# vixen-64k.net
KiCad netlist of a schematic drawn in EAGLE
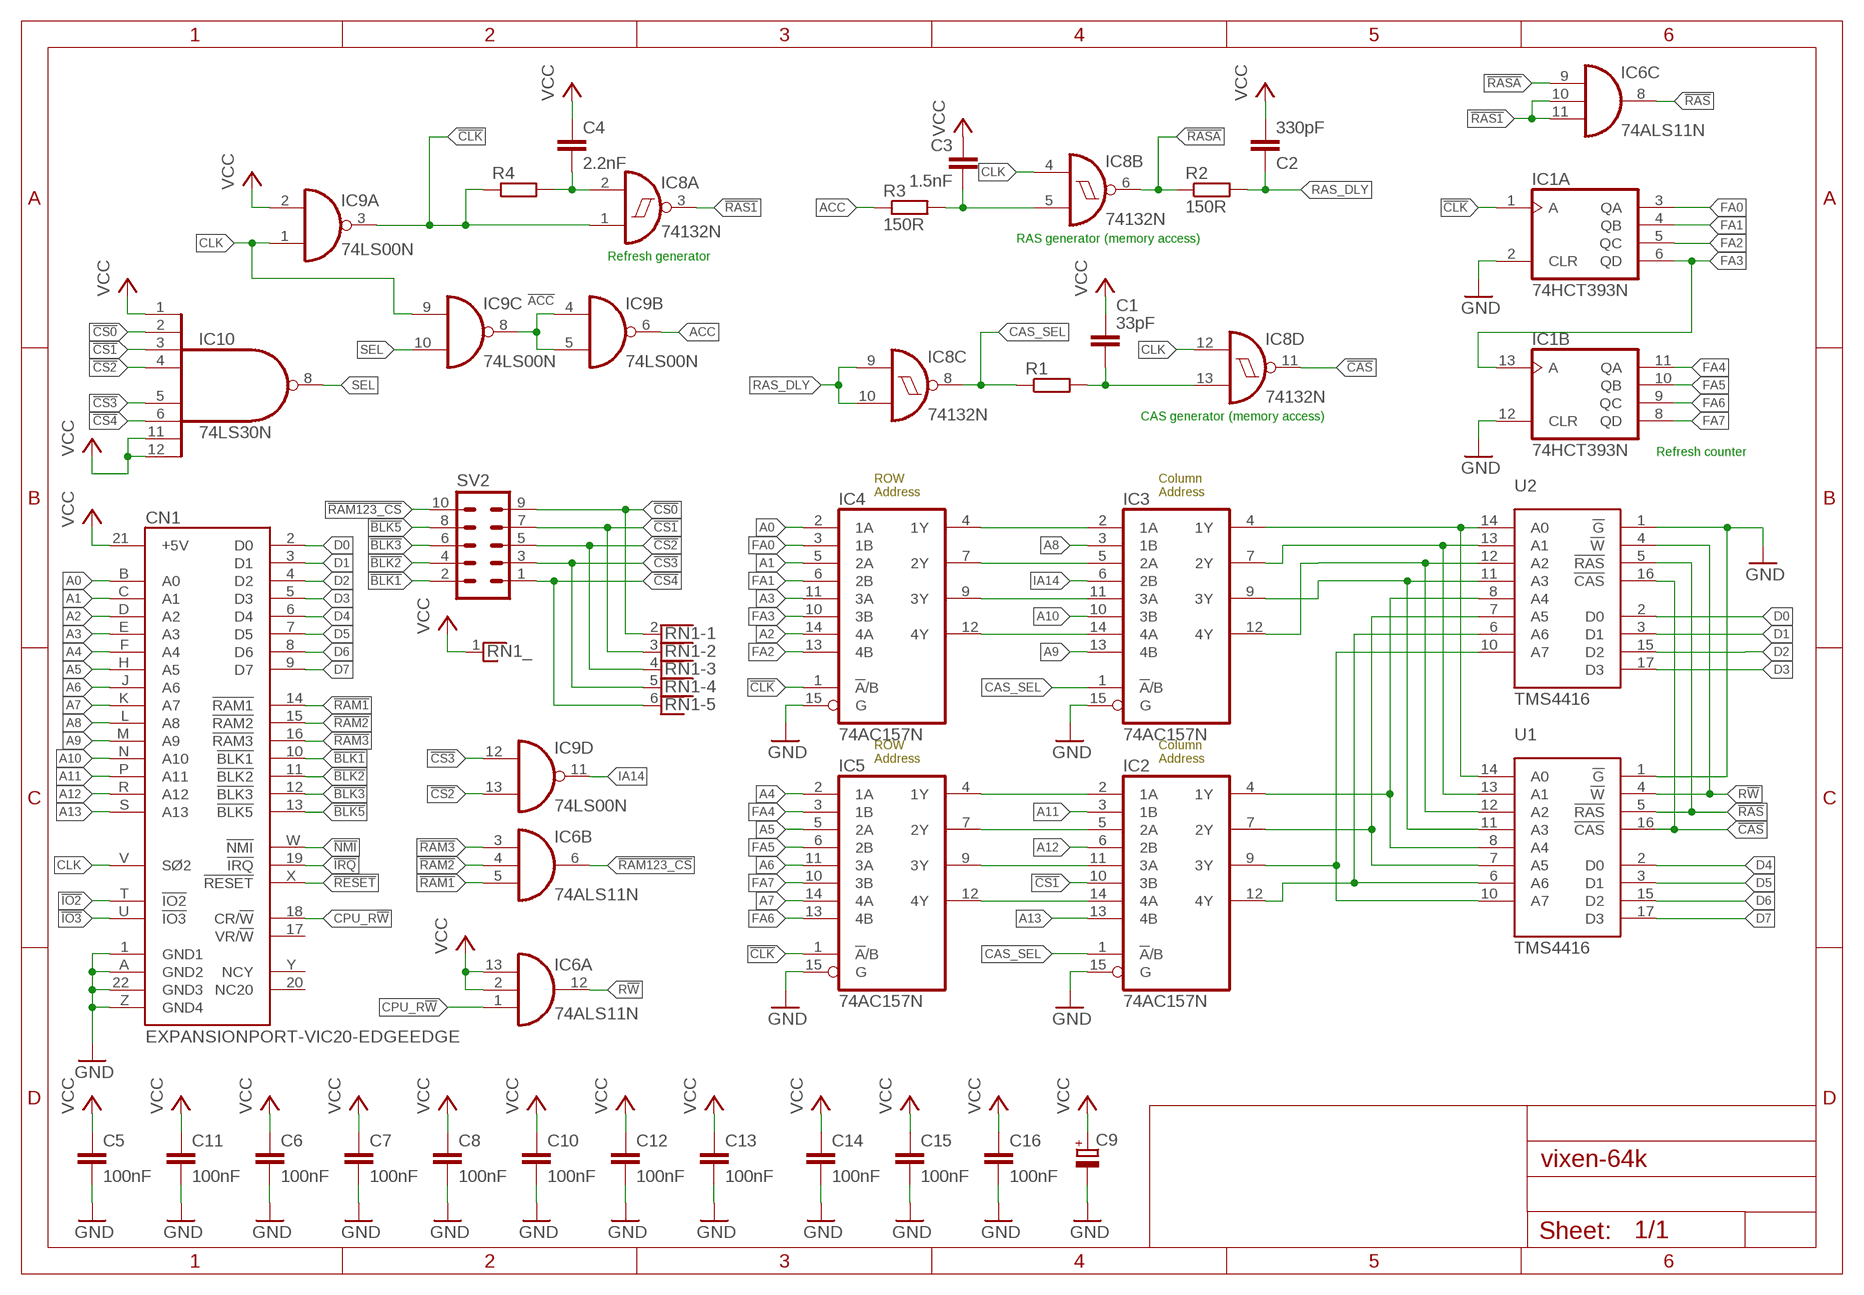
[diagram p0: schematic, sheet 1]

(export (version "E")
  (design (tool "Eeschema 10.0.6"))
  (components
    (comp (ref "C1")
      (value "33pF")
      (footprint "eagle-import:C025-025X050")
      (libsource (lib "eagle-import") (part "C-EU025-025X050"))
    )
    (comp (ref "C2")
      (value "330pF")
      (footprint "eagle-import:C025-025X050")
      (libsource (lib "eagle-import") (part "C-EU025-025X050"))
    )
    (comp (ref "C3")
      (value "1.5nF")
      (footprint "eagle-import:C025-025X050")
      (libsource (lib "eagle-import") (part "C-EU025-025X050"))
    )
    (comp (ref "C4")
      (value "2.2nF")
      (footprint "eagle-import:C025-025X050")
      (libsource (lib "eagle-import") (part "C-EU025-025X050"))
    )
    (comp (ref "C5")
      (value "100nF")
      (footprint "eagle-import:C025-025X050")
      (libsource (lib "eagle-import") (part "C-EU025-025X050"))
    )
    (comp (ref "C6")
      (value "100nF")
      (footprint "eagle-import:C025-025X050")
      (libsource (lib "eagle-import") (part "C-EU025-025X050"))
    )
    (comp (ref "C7")
      (value "100nF")
      (footprint "eagle-import:C025-025X050")
      (libsource (lib "eagle-import") (part "C-EU025-025X050"))
    )
    (comp (ref "C8")
      (value "100nF")
      (footprint "eagle-import:C025-025X050")
      (libsource (lib "eagle-import") (part "C-EU025-025X050"))
    )
    (comp (ref "C9")
      (value "CPOL-EUE15-5AXIAL")
      (footprint "eagle-import:E15-5")
      (libsource (lib "eagle-import") (part "CPOL-EUE15-5AXIAL"))
    )
    (comp (ref "C10")
      (value "100nF")
      (footprint "eagle-import:C025-025X050")
      (libsource (lib "eagle-import") (part "C-EU025-025X050"))
    )
    (comp (ref "C11")
      (value "100nF")
      (footprint "eagle-import:C025-025X050")
      (libsource (lib "eagle-import") (part "C-EU025-025X050"))
    )
    (comp (ref "C12")
      (value "100nF")
      (footprint "eagle-import:C025-025X050")
      (libsource (lib "eagle-import") (part "C-EU025-025X050"))
    )
    (comp (ref "C13")
      (value "100nF")
      (footprint "eagle-import:C025-025X050")
      (libsource (lib "eagle-import") (part "C-EU025-025X050"))
    )
    (comp (ref "C14")
      (value "100nF")
      (footprint "eagle-import:C025-025X050")
      (libsource (lib "eagle-import") (part "C-EU025-025X050"))
    )
    (comp (ref "C15")
      (value "100nF")
      (footprint "eagle-import:C025-025X050")
      (libsource (lib "eagle-import") (part "C-EU025-025X050"))
    )
    (comp (ref "C16")
      (value "100nF")
      (footprint "eagle-import:C025-025X050")
      (libsource (lib "eagle-import") (part "C-EU025-025X050"))
    )
    (comp (ref "CN1")
      (value "EXPANSIONPORT-VIC20-EDGEEDGE")
      (footprint "eagle-import:UPS44EDGE")
      (libsource (lib "eagle-import") (part "EXPANSIONPORT-VIC20-EDGEEDGE"))
    )
    (comp (ref "IC1")
      (value "74HCT393N")
      (footprint "eagle-import:DIL14")
      (libsource (lib "eagle-import") (part "74393NHCT"))
    )
    (comp (ref "IC2")
      (value "74AC157N")
      (footprint "eagle-import:DIL16")
      (libsource (lib "eagle-import") (part "74157NAC"))
    )
    (comp (ref "IC3")
      (value "74AC157N")
      (footprint "eagle-import:DIL16")
      (libsource (lib "eagle-import") (part "74157NAC"))
    )
    (comp (ref "IC4")
      (value "74AC157N")
      (footprint "eagle-import:DIL16")
      (libsource (lib "eagle-import") (part "74157NAC"))
    )
    (comp (ref "IC5")
      (value "74AC157N")
      (footprint "eagle-import:DIL16")
      (libsource (lib "eagle-import") (part "74157NAC"))
    )
    (comp (ref "IC6")
      (value "74ALS11N")
      (footprint "eagle-import:DIL14")
      (libsource (lib "eagle-import") (part "7411NALS"))
    )
    (comp (ref "IC8")
      (value "74132N")
      (footprint "eagle-import:DIL14")
      (libsource (lib "eagle-import") (part "74132N"))
    )
    (comp (ref "IC9")
      (value "74LS00N")
      (footprint "eagle-import:DIL14")
      (libsource (lib "eagle-import") (part "7400NLS"))
    )
    (comp (ref "IC10")
      (value "74LS30N")
      (footprint "eagle-import:DIL14")
      (libsource (lib "eagle-import") (part "7430NLS"))
    )
    (comp (ref "R1")
      (value "R-EU_0204/7")
      (footprint "eagle-import:0204_7")
      (libsource (lib "eagle-import") (part "R-EU_0204/7"))
    )
    (comp (ref "R2")
      (value "150R")
      (footprint "eagle-import:0204_7")
      (libsource (lib "eagle-import") (part "R-EU_0204/7"))
    )
    (comp (ref "R3")
      (value "150R")
      (footprint "eagle-import:0204_7")
      (libsource (lib "eagle-import") (part "R-EU_0204/7"))
    )
    (comp (ref "R4")
      (value "R-EU_0204/7")
      (footprint "eagle-import:0204_7")
      (libsource (lib "eagle-import") (part "R-EU_0204/7"))
    )
    (comp (ref "RN1")
      (value "RNX5")
      (footprint "eagle-import:RN-6")
      (libsource (lib "eagle-import") (part "RNX5"))
    )
    (comp (ref "SV2")
      (value "MA05-2")
      (footprint "eagle-import:MA05-2")
      (libsource (lib "eagle-import") (part "MA05-2"))
    )
    (comp (ref "U1")
      (value "TMS4416")
      (footprint "eagle-import:DIL18")
      (libsource (lib "eagle-import") (part "TMS4416"))
    )
    (comp (ref "U2")
      (value "TMS4416")
      (footprint "eagle-import:DIL18")
      (libsource (lib "eagle-import") (part "TMS4416"))
    )
  )
  (nets
    (net (code "1") (name "/CPU_R~{W}") (class "Default")
      (node (ref "CN1") (pin "18") (pinfunction "CR/~{W}_18") (pintype "output"))
      (node (ref "IC6") (pin "1") (pinfunction "I0_1") (pintype "input"))
    )
    (net (code "2") (name "/R~{W}") (class "Default")
      (node (ref "IC6") (pin "12") (pinfunction "O_12") (pintype "output"))
      (node (ref "U1") (pin "4") (pinfunction "~{W}_4") (pintype "bidirectional"))
      (node (ref "U2") (pin "4") (pinfunction "~{W}_4") (pintype "bidirectional"))
    )
    (net (code "3") (name "/~{ACC}") (class "Default")
      (node (ref "IC9") (pin "4") (pinfunction "I0_4") (pintype "input"))
      (node (ref "IC9") (pin "5") (pinfunction "I1_5") (pintype "input"))
      (node (ref "IC9") (pin "8") (pinfunction "O_8") (pintype "output"))
    )
    (net (code "4") (name "/~{BLK1}") (class "Default")
      (node (ref "CN1") (pin "10") (pinfunction "~{BLK1}_10") (pintype "output"))
      (node (ref "SV2") (pin "2") (pinfunction "2_2") (pintype "passive"))
    )
    (net (code "5") (name "/~{BLK2}") (class "Default")
      (node (ref "CN1") (pin "11") (pinfunction "~{BLK2}_11") (pintype "output"))
      (node (ref "SV2") (pin "4") (pinfunction "4_4") (pintype "passive"))
    )
    (net (code "6") (name "/~{BLK3}") (class "Default")
      (node (ref "CN1") (pin "12") (pinfunction "~{BLK3}_12") (pintype "output"))
      (node (ref "SV2") (pin "6") (pinfunction "6_6") (pintype "passive"))
    )
    (net (code "7") (name "/~{BLK5}") (class "Default")
      (node (ref "CN1") (pin "13") (pinfunction "~{BLK5}_13") (pintype "output"))
      (node (ref "SV2") (pin "8") (pinfunction "8_8") (pintype "passive"))
    )
    (net (code "8") (name "/~{CAS}") (class "Default")
      (node (ref "IC8") (pin "11") (pinfunction "O_11") (pintype "output"))
      (node (ref "U1") (pin "16") (pinfunction "~{CAS}_16") (pintype "bidirectional"))
      (node (ref "U2") (pin "16") (pinfunction "~{CAS}_16") (pintype "bidirectional"))
    )
    (net (code "9") (name "/~{CLK}") (class "Default")
      (node (ref "IC1") (pin "1") (pinfunction "A_1") (pintype "input"))
      (node (ref "IC4") (pin "1") (pinfunction "~{A}/B_1") (pintype "input"))
      (node (ref "IC5") (pin "1") (pinfunction "~{A}/B_1") (pintype "input"))
      (node (ref "IC8") (pin "1") (pinfunction "I0_1") (pintype "input"))
      (node (ref "IC9") (pin "3") (pinfunction "O_3") (pintype "output"))
      (node (ref "R4") (pin "1") (pinfunction "1_1") (pintype "passive"))
    )
    (net (code "10") (name "/~{CS0}") (class "Default")
      (node (ref "IC10") (pin "2") (pinfunction "I1_2") (pintype "input"))
      (node (ref "RN1") (pin "2") (pinfunction "1_2") (pintype "passive"))
      (node (ref "SV2") (pin "9") (pinfunction "9_9") (pintype "passive"))
    )
    (net (code "11") (name "/~{CS1}") (class "Default")
      (node (ref "IC10") (pin "3") (pinfunction "I2_3") (pintype "input"))
      (node (ref "IC2") (pin "10") (pinfunction "3B_10") (pintype "input"))
      (node (ref "RN1") (pin "3") (pinfunction "1_3") (pintype "passive"))
      (node (ref "SV2") (pin "7") (pinfunction "7_7") (pintype "passive"))
    )
    (net (code "12") (name "/~{CS2}") (class "Default")
      (node (ref "IC10") (pin "4") (pinfunction "I3_4") (pintype "input"))
      (node (ref "IC9") (pin "13") (pinfunction "I1_13") (pintype "input"))
      (node (ref "RN1") (pin "4") (pinfunction "1_4") (pintype "passive"))
      (node (ref "SV2") (pin "5") (pinfunction "5_5") (pintype "passive"))
    )
    (net (code "13") (name "/~{CS3}") (class "Default")
      (node (ref "IC10") (pin "5") (pinfunction "I4_5") (pintype "input"))
      (node (ref "IC9") (pin "12") (pinfunction "I0_12") (pintype "input"))
      (node (ref "RN1") (pin "5") (pinfunction "1_5") (pintype "passive"))
      (node (ref "SV2") (pin "3") (pinfunction "3_3") (pintype "passive"))
    )
    (net (code "14") (name "/~{CS4}") (class "Default")
      (node (ref "IC10") (pin "6") (pinfunction "I5_6") (pintype "input"))
      (node (ref "RN1") (pin "6") (pinfunction "1_6") (pintype "passive"))
      (node (ref "SV2") (pin "1") (pinfunction "1_1") (pintype "passive"))
    )
    (net (code "15") (name "/~{IO2}") (class "Default")
      (node (ref "CN1") (pin "T") (pinfunction "~{IO2}_T") (pintype "output"))
    )
    (net (code "16") (name "/~{IO3}") (class "Default")
      (node (ref "CN1") (pin "U") (pinfunction "~{IO3}_U") (pintype "output"))
    )
    (net (code "17") (name "/~{IRQ}") (class "Default")
      (node (ref "CN1") (pin "19") (pinfunction "~{IRQ}_19") (pintype "bidirectional"))
    )
    (net (code "18") (name "/~{NMI}") (class "Default")
      (node (ref "CN1") (pin "W") (pinfunction "~{NMI}_W") (pintype "bidirectional"))
    )
    (net (code "19") (name "/~{RAM1}") (class "Default")
      (node (ref "CN1") (pin "14") (pinfunction "~{RAM1}_14") (pintype "output"))
      (node (ref "IC6") (pin "5") (pinfunction "I2_5") (pintype "input"))
    )
    (net (code "20") (name "/~{RAM2}") (class "Default")
      (node (ref "CN1") (pin "15") (pinfunction "~{RAM2}_15") (pintype "output"))
      (node (ref "IC6") (pin "4") (pinfunction "I1_4") (pintype "input"))
    )
    (net (code "21") (name "/~{RAM3}") (class "Default")
      (node (ref "CN1") (pin "16") (pinfunction "~{RAM3}_16") (pintype "output"))
      (node (ref "IC6") (pin "3") (pinfunction "I0_3") (pintype "input"))
    )
    (net (code "22") (name "/~{RAM123_CS}") (class "Default")
      (node (ref "IC6") (pin "6") (pinfunction "O_6") (pintype "output"))
      (node (ref "SV2") (pin "10") (pinfunction "10_10") (pintype "passive"))
    )
    (net (code "23") (name "/~{RAS1}") (class "Default")
      (node (ref "IC6") (pin "10") (pinfunction "I1_10") (pintype "input"))
      (node (ref "IC6") (pin "11") (pinfunction "I2_11") (pintype "input"))
      (node (ref "IC8") (pin "3") (pinfunction "O_3") (pintype "output"))
    )
    (net (code "24") (name "/~{RASA}") (class "Default")
      (node (ref "IC6") (pin "9") (pinfunction "I0_9") (pintype "input"))
      (node (ref "IC8") (pin "6") (pinfunction "O_6") (pintype "output"))
      (node (ref "R2") (pin "1") (pinfunction "1_1") (pintype "passive"))
    )
    (net (code "25") (name "/~{RAS}") (class "Default")
      (node (ref "IC6") (pin "8") (pinfunction "O_8") (pintype "output"))
      (node (ref "U1") (pin "5") (pinfunction "~{RAS}_5") (pintype "bidirectional"))
      (node (ref "U2") (pin "5") (pinfunction "~{RAS}_5") (pintype "bidirectional"))
    )
    (net (code "26") (name "/~{RESET}") (class "Default")
      (node (ref "CN1") (pin "X") (pinfunction "~{RESET}_X") (pintype "bidirectional"))
    )
    (net (code "27") (name "A0") (class "Default")
      (node (ref "CN1") (pin "B") (pinfunction "A0_B") (pintype "output"))
      (node (ref "IC4") (pin "2") (pinfunction "1A_2") (pintype "input"))
    )
    (net (code "28") (name "A1") (class "Default")
      (node (ref "CN1") (pin "C") (pinfunction "A1_C") (pintype "output"))
      (node (ref "IC4") (pin "5") (pinfunction "2A_5") (pintype "input"))
    )
    (net (code "29") (name "A2") (class "Default")
      (node (ref "CN1") (pin "D") (pinfunction "A2_D") (pintype "output"))
      (node (ref "IC4") (pin "14") (pinfunction "4A_14") (pintype "input"))
    )
    (net (code "30") (name "A3") (class "Default")
      (node (ref "CN1") (pin "E") (pinfunction "A3_E") (pintype "output"))
      (node (ref "IC4") (pin "11") (pinfunction "3A_11") (pintype "input"))
    )
    (net (code "31") (name "A4") (class "Default")
      (node (ref "CN1") (pin "F") (pinfunction "A4_F") (pintype "output"))
      (node (ref "IC5") (pin "2") (pinfunction "1A_2") (pintype "input"))
    )
    (net (code "32") (name "A5") (class "Default")
      (node (ref "CN1") (pin "H") (pinfunction "A5_H") (pintype "output"))
      (node (ref "IC5") (pin "5") (pinfunction "2A_5") (pintype "input"))
    )
    (net (code "33") (name "A6") (class "Default")
      (node (ref "CN1") (pin "J") (pinfunction "A6_J") (pintype "output"))
      (node (ref "IC5") (pin "11") (pinfunction "3A_11") (pintype "input"))
    )
    (net (code "34") (name "A7") (class "Default")
      (node (ref "CN1") (pin "K") (pinfunction "A7_K") (pintype "output"))
      (node (ref "IC5") (pin "14") (pinfunction "4A_14") (pintype "input"))
    )
    (net (code "35") (name "A8") (class "Default")
      (node (ref "CN1") (pin "L") (pinfunction "A8_L") (pintype "output"))
      (node (ref "IC3") (pin "3") (pinfunction "1B_3") (pintype "input"))
    )
    (net (code "36") (name "A9") (class "Default")
      (node (ref "CN1") (pin "M") (pinfunction "A9_M") (pintype "output"))
      (node (ref "IC3") (pin "13") (pinfunction "4B_13") (pintype "input"))
    )
    (net (code "37") (name "A10") (class "Default")
      (node (ref "CN1") (pin "N") (pinfunction "A10_N") (pintype "output"))
      (node (ref "IC3") (pin "10") (pinfunction "3B_10") (pintype "input"))
    )
    (net (code "38") (name "A11") (class "Default")
      (node (ref "CN1") (pin "P") (pinfunction "A11_P") (pintype "output"))
      (node (ref "IC2") (pin "3") (pinfunction "1B_3") (pintype "input"))
    )
    (net (code "39") (name "A12") (class "Default")
      (node (ref "CN1") (pin "R") (pinfunction "A12_R") (pintype "output"))
      (node (ref "IC2") (pin "6") (pinfunction "2B_6") (pintype "input"))
    )
    (net (code "40") (name "A13") (class "Default")
      (node (ref "CN1") (pin "S") (pinfunction "A13_S") (pintype "output"))
      (node (ref "IC2") (pin "13") (pinfunction "4B_13") (pintype "input"))
    )
    (net (code "41") (name "ACC") (class "Default")
      (node (ref "IC9") (pin "6") (pinfunction "O_6") (pintype "output"))
      (node (ref "R3") (pin "1") (pinfunction "1_1") (pintype "passive"))
    )
    (net (code "42") (name "CAS_SEL") (class "Default")
      (node (ref "IC2") (pin "1") (pinfunction "~{A}/B_1") (pintype "input"))
      (node (ref "IC3") (pin "1") (pinfunction "~{A}/B_1") (pintype "input"))
      (node (ref "IC8") (pin "8") (pinfunction "O_8") (pintype "output"))
      (node (ref "R1") (pin "1") (pinfunction "1_1") (pintype "passive"))
    )
    (net (code "43") (name "CLK") (class "Default")
      (node (ref "CN1") (pin "V") (pinfunction "SØ2_V") (pintype "output"))
      (node (ref "IC8") (pin "12") (pinfunction "I0_12") (pintype "input"))
      (node (ref "IC8") (pin "4") (pinfunction "I0_4") (pintype "input"))
      (node (ref "IC9") (pin "1") (pinfunction "I0_1") (pintype "input"))
      (node (ref "IC9") (pin "9") (pinfunction "I0_9") (pintype "input"))
    )
    (net (code "44") (name "D0") (class "Default")
      (node (ref "CN1") (pin "2") (pinfunction "D0_2") (pintype "bidirectional"))
      (node (ref "U2") (pin "2") (pinfunction "D0_2") (pintype "bidirectional"))
    )
    (net (code "45") (name "D1") (class "Default")
      (node (ref "CN1") (pin "3") (pinfunction "D1_3") (pintype "bidirectional"))
      (node (ref "U2") (pin "3") (pinfunction "D1_3") (pintype "bidirectional"))
    )
    (net (code "46") (name "D2") (class "Default")
      (node (ref "CN1") (pin "4") (pinfunction "D2_4") (pintype "bidirectional"))
      (node (ref "U2") (pin "15") (pinfunction "D2_15") (pintype "bidirectional"))
    )
    (net (code "47") (name "D3") (class "Default")
      (node (ref "CN1") (pin "5") (pinfunction "D3_5") (pintype "bidirectional"))
      (node (ref "U2") (pin "17") (pinfunction "D3_17") (pintype "bidirectional"))
    )
    (net (code "48") (name "D4") (class "Default")
      (node (ref "CN1") (pin "6") (pinfunction "D4_6") (pintype "bidirectional"))
      (node (ref "U1") (pin "2") (pinfunction "D0_2") (pintype "bidirectional"))
    )
    (net (code "49") (name "D5") (class "Default")
      (node (ref "CN1") (pin "7") (pinfunction "D5_7") (pintype "bidirectional"))
      (node (ref "U1") (pin "3") (pinfunction "D1_3") (pintype "bidirectional"))
    )
    (net (code "50") (name "D6") (class "Default")
      (node (ref "CN1") (pin "8") (pinfunction "D6_8") (pintype "bidirectional"))
      (node (ref "U1") (pin "15") (pinfunction "D2_15") (pintype "bidirectional"))
    )
    (net (code "51") (name "D7") (class "Default")
      (node (ref "CN1") (pin "9") (pinfunction "D7_9") (pintype "bidirectional"))
      (node (ref "U1") (pin "17") (pinfunction "D3_17") (pintype "bidirectional"))
    )
    (net (code "52") (name "FA0") (class "Default")
      (node (ref "IC1") (pin "3") (pinfunction "QA_3") (pintype "output"))
      (node (ref "IC4") (pin "3") (pinfunction "1B_3") (pintype "input"))
    )
    (net (code "53") (name "FA1") (class "Default")
      (node (ref "IC1") (pin "4") (pinfunction "QB_4") (pintype "output"))
      (node (ref "IC4") (pin "6") (pinfunction "2B_6") (pintype "input"))
    )
    (net (code "54") (name "FA2") (class "Default")
      (node (ref "IC1") (pin "5") (pinfunction "QC_5") (pintype "output"))
      (node (ref "IC4") (pin "13") (pinfunction "4B_13") (pintype "input"))
    )
    (net (code "55") (name "FA3") (class "Default")
      (node (ref "IC1") (pin "13") (pinfunction "A_13") (pintype "input"))
      (node (ref "IC1") (pin "6") (pinfunction "QD_6") (pintype "output"))
      (node (ref "IC4") (pin "10") (pinfunction "3B_10") (pintype "input"))
    )
    (net (code "56") (name "FA4") (class "Default")
      (node (ref "IC1") (pin "11") (pinfunction "QA_11") (pintype "output"))
      (node (ref "IC5") (pin "3") (pinfunction "1B_3") (pintype "input"))
    )
    (net (code "57") (name "FA5") (class "Default")
      (node (ref "IC1") (pin "10") (pinfunction "QB_10") (pintype "output"))
      (node (ref "IC5") (pin "6") (pinfunction "2B_6") (pintype "input"))
    )
    (net (code "58") (name "FA6") (class "Default")
      (node (ref "IC1") (pin "9") (pinfunction "QC_9") (pintype "output"))
      (node (ref "IC5") (pin "13") (pinfunction "4B_13") (pintype "input"))
    )
    (net (code "59") (name "FA7") (class "Default")
      (node (ref "IC1") (pin "8") (pinfunction "QD_8") (pintype "output"))
      (node (ref "IC5") (pin "10") (pinfunction "3B_10") (pintype "input"))
    )
    (net (code "60") (name "GND") (class "Default")
      (node (ref "C10") (pin "2") (pinfunction "2_2") (pintype "passive"))
      (node (ref "C11") (pin "2") (pinfunction "2_2") (pintype "passive"))
      (node (ref "C12") (pin "2") (pinfunction "2_2") (pintype "passive"))
      (node (ref "C13") (pin "2") (pinfunction "2_2") (pintype "passive"))
      (node (ref "C14") (pin "2") (pinfunction "2_2") (pintype "passive"))
      (node (ref "C15") (pin "2") (pinfunction "2_2") (pintype "passive"))
      (node (ref "C16") (pin "2") (pinfunction "2_2") (pintype "passive"))
      (node (ref "C5") (pin "2") (pinfunction "2_2") (pintype "passive"))
      (node (ref "C6") (pin "2") (pinfunction "2_2") (pintype "passive"))
      (node (ref "C7") (pin "2") (pinfunction "2_2") (pintype "passive"))
      (node (ref "C8") (pin "2") (pinfunction "2_2") (pintype "passive"))
      (node (ref "C9") (pin "-") (pinfunction "-_-") (pintype "passive"))
      (node (ref "CN1") (pin "1") (pinfunction "GND1_1") (pintype "passive"))
      (node (ref "CN1") (pin "22") (pinfunction "GND3_22") (pintype "passive"))
      (node (ref "CN1") (pin "A") (pinfunction "GND2_A") (pintype "passive"))
      (node (ref "CN1") (pin "Z") (pinfunction "GND4_Z") (pintype "passive"))
      (node (ref "IC1") (pin "12") (pinfunction "CLR_12") (pintype "input"))
      (node (ref "IC1") (pin "2") (pinfunction "CLR_2") (pintype "input"))
      (node (ref "IC2") (pin "15") (pinfunction "G_15") (pintype "input"))
      (node (ref "IC3") (pin "15") (pinfunction "G_15") (pintype "input"))
      (node (ref "IC4") (pin "15") (pinfunction "G_15") (pintype "input"))
      (node (ref "IC5") (pin "15") (pinfunction "G_15") (pintype "input"))
      (node (ref "U1") (pin "1") (pinfunction "~{G}_1") (pintype "bidirectional"))
      (node (ref "U2") (pin "1") (pinfunction "~{G}_1") (pintype "bidirectional"))
    )
    (net (code "61") (name "IA14") (class "Default")
      (node (ref "IC3") (pin "6") (pinfunction "2B_6") (pintype "input"))
      (node (ref "IC9") (pin "11") (pinfunction "O_11") (pintype "output"))
    )
    (net (code "62") (name "Net-(IC2A-1A)") (class "Default")
      (node (ref "IC2") (pin "2") (pinfunction "1A_2") (pintype "input"))
      (node (ref "IC5") (pin "4") (pinfunction "1Y_4") (pintype "output"))
    )
    (net (code "63") (name "Net-(IC2A-1Y)") (class "Default")
      (node (ref "IC2") (pin "4") (pinfunction "1Y_4") (pintype "output"))
      (node (ref "U1") (pin "8") (pinfunction "A4_8") (pintype "input"))
      (node (ref "U2") (pin "8") (pinfunction "A4_8") (pintype "input"))
    )
    (net (code "64") (name "Net-(IC2A-2A)") (class "Default")
      (node (ref "IC2") (pin "5") (pinfunction "2A_5") (pintype "input"))
      (node (ref "IC5") (pin "7") (pinfunction "2Y_7") (pintype "output"))
    )
    (net (code "65") (name "Net-(IC2A-2Y)") (class "Default")
      (node (ref "IC2") (pin "7") (pinfunction "2Y_7") (pintype "output"))
      (node (ref "U1") (pin "7") (pinfunction "A5_7") (pintype "input"))
      (node (ref "U2") (pin "7") (pinfunction "A5_7") (pintype "input"))
    )
    (net (code "66") (name "Net-(IC2A-3A)") (class "Default")
      (node (ref "IC2") (pin "11") (pinfunction "3A_11") (pintype "input"))
      (node (ref "IC5") (pin "9") (pinfunction "3Y_9") (pintype "output"))
    )
    (net (code "67") (name "Net-(IC2A-3Y)") (class "Default")
      (node (ref "IC2") (pin "9") (pinfunction "3Y_9") (pintype "output"))
      (node (ref "U1") (pin "10") (pinfunction "A7_10") (pintype "input"))
      (node (ref "U2") (pin "10") (pinfunction "A7_10") (pintype "input"))
    )
    (net (code "68") (name "Net-(IC2A-4A)") (class "Default")
      (node (ref "IC2") (pin "14") (pinfunction "4A_14") (pintype "input"))
      (node (ref "IC5") (pin "12") (pinfunction "4Y_12") (pintype "output"))
    )
    (net (code "69") (name "Net-(IC2A-4Y)") (class "Default")
      (node (ref "IC2") (pin "12") (pinfunction "4Y_12") (pintype "output"))
      (node (ref "U1") (pin "6") (pinfunction "A6_6") (pintype "input"))
      (node (ref "U2") (pin "6") (pinfunction "A6_6") (pintype "input"))
    )
    (net (code "70") (name "Net-(IC3A-1A)") (class "Default")
      (node (ref "IC3") (pin "2") (pinfunction "1A_2") (pintype "input"))
      (node (ref "IC4") (pin "4") (pinfunction "1Y_4") (pintype "output"))
    )
    (net (code "71") (name "Net-(IC3A-1Y)") (class "Default")
      (node (ref "IC3") (pin "4") (pinfunction "1Y_4") (pintype "output"))
      (node (ref "U1") (pin "14") (pinfunction "A0_14") (pintype "input"))
      (node (ref "U2") (pin "14") (pinfunction "A0_14") (pintype "input"))
    )
    (net (code "72") (name "Net-(IC3A-2A)") (class "Default")
      (node (ref "IC3") (pin "5") (pinfunction "2A_5") (pintype "input"))
      (node (ref "IC4") (pin "7") (pinfunction "2Y_7") (pintype "output"))
    )
    (net (code "73") (name "Net-(IC3A-2Y)") (class "Default")
      (node (ref "IC3") (pin "7") (pinfunction "2Y_7") (pintype "output"))
      (node (ref "U1") (pin "13") (pinfunction "A1_13") (pintype "input"))
      (node (ref "U2") (pin "13") (pinfunction "A1_13") (pintype "input"))
    )
    (net (code "74") (name "Net-(IC3A-3A)") (class "Default")
      (node (ref "IC3") (pin "11") (pinfunction "3A_11") (pintype "input"))
      (node (ref "IC4") (pin "9") (pinfunction "3Y_9") (pintype "output"))
    )
    (net (code "75") (name "Net-(IC3A-3Y)") (class "Default")
      (node (ref "IC3") (pin "9") (pinfunction "3Y_9") (pintype "output"))
      (node (ref "U1") (pin "11") (pinfunction "A3_11") (pintype "input"))
      (node (ref "U2") (pin "11") (pinfunction "A3_11") (pintype "input"))
    )
    (net (code "76") (name "Net-(IC3A-4A)") (class "Default")
      (node (ref "IC3") (pin "14") (pinfunction "4A_14") (pintype "input"))
      (node (ref "IC4") (pin "12") (pinfunction "4Y_12") (pintype "output"))
    )
    (net (code "77") (name "Net-(IC3A-4Y)") (class "Default")
      (node (ref "IC3") (pin "12") (pinfunction "4Y_12") (pintype "output"))
      (node (ref "U1") (pin "12") (pinfunction "A2_12") (pintype "input"))
      (node (ref "U2") (pin "12") (pinfunction "A2_12") (pintype "input"))
    )
    (net (code "78") (name "Net-(IC8A-I1)") (class "Default")
      (node (ref "C4") (pin "2") (pinfunction "2_2") (pintype "passive"))
      (node (ref "IC8") (pin "2") (pinfunction "I1_2") (pintype "input"))
      (node (ref "R4") (pin "2") (pinfunction "2_2") (pintype "passive"))
    )
    (net (code "79") (name "Net-(IC8B-I1)") (class "Default")
      (node (ref "C3") (pin "2") (pinfunction "2_2") (pintype "passive"))
      (node (ref "IC8") (pin "5") (pinfunction "I1_5") (pintype "input"))
      (node (ref "R3") (pin "2") (pinfunction "2_2") (pintype "passive"))
    )
    (net (code "80") (name "Net-(IC8D-I1)") (class "Default")
      (node (ref "C1") (pin "2") (pinfunction "2_2") (pintype "passive"))
      (node (ref "IC8") (pin "13") (pinfunction "I1_13") (pintype "input"))
      (node (ref "R1") (pin "2") (pinfunction "2_2") (pintype "passive"))
    )
    (net (code "81") (name "RAS_DLY") (class "Default")
      (node (ref "C2") (pin "1") (pinfunction "1_1") (pintype "passive"))
      (node (ref "IC8") (pin "10") (pinfunction "I1_10") (pintype "input"))
      (node (ref "IC8") (pin "9") (pinfunction "I0_9") (pintype "input"))
      (node (ref "R2") (pin "2") (pinfunction "2_2") (pintype "passive"))
    )
    (net (code "82") (name "SEL") (class "Default")
      (node (ref "IC10") (pin "8") (pinfunction "O_8") (pintype "output"))
      (node (ref "IC9") (pin "10") (pinfunction "I1_10") (pintype "input"))
    )
    (net (code "83") (name "VCC") (class "Default")
      (node (ref "C1") (pin "1") (pinfunction "1_1") (pintype "passive"))
      (node (ref "C10") (pin "1") (pinfunction "1_1") (pintype "passive"))
      (node (ref "C11") (pin "1") (pinfunction "1_1") (pintype "passive"))
      (node (ref "C12") (pin "1") (pinfunction "1_1") (pintype "passive"))
      (node (ref "C13") (pin "1") (pinfunction "1_1") (pintype "passive"))
      (node (ref "C14") (pin "1") (pinfunction "1_1") (pintype "passive"))
      (node (ref "C15") (pin "1") (pinfunction "1_1") (pintype "passive"))
      (node (ref "C16") (pin "1") (pinfunction "1_1") (pintype "passive"))
      (node (ref "C2") (pin "2") (pinfunction "2_2") (pintype "passive"))
      (node (ref "C3") (pin "1") (pinfunction "1_1") (pintype "passive"))
      (node (ref "C4") (pin "1") (pinfunction "1_1") (pintype "passive"))
      (node (ref "C5") (pin "1") (pinfunction "1_1") (pintype "passive"))
      (node (ref "C6") (pin "1") (pinfunction "1_1") (pintype "passive"))
      (node (ref "C7") (pin "1") (pinfunction "1_1") (pintype "passive"))
      (node (ref "C8") (pin "1") (pinfunction "1_1") (pintype "passive"))
      (node (ref "C9") (pin "+") (pinfunction "+_+") (pintype "passive"))
      (node (ref "CN1") (pin "21") (pinfunction "+5V_21") (pintype "power_in"))
      (node (ref "IC10") (pin "1") (pinfunction "I0_1") (pintype "input"))
      (node (ref "IC10") (pin "11") (pinfunction "I6_11") (pintype "input"))
      (node (ref "IC10") (pin "12") (pinfunction "I7_12") (pintype "input"))
      (node (ref "IC6") (pin "13") (pinfunction "I2_13") (pintype "input"))
      (node (ref "IC6") (pin "2") (pinfunction "I1_2") (pintype "input"))
      (node (ref "IC9") (pin "2") (pinfunction "I1_2") (pintype "input"))
      (node (ref "RN1") (pin "1") (pinfunction "1_1") (pintype "passive"))
    )
    (net (code "84") (name "unconnected-(CN1-NC20-Pad20)") (class "Default")
      (node (ref "CN1") (pin "20") (pinfunction "NC20_20") (pintype "passive"))
    )
    (net (code "85") (name "unconnected-(CN1-NCY-PadY)") (class "Default")
      (node (ref "CN1") (pin "Y") (pinfunction "NCY_Y") (pintype "passive"))
    )
    (net (code "86") (name "unconnected-(CN1-VR{slash}~{W}-Pad17)") (class "Default")
      (node (ref "CN1") (pin "17") (pinfunction "VR/~{W}_17") (pintype "output"))
    )
  )
)
